# Main.net
KiCad netlist of a schematic drawn in Altium Designer
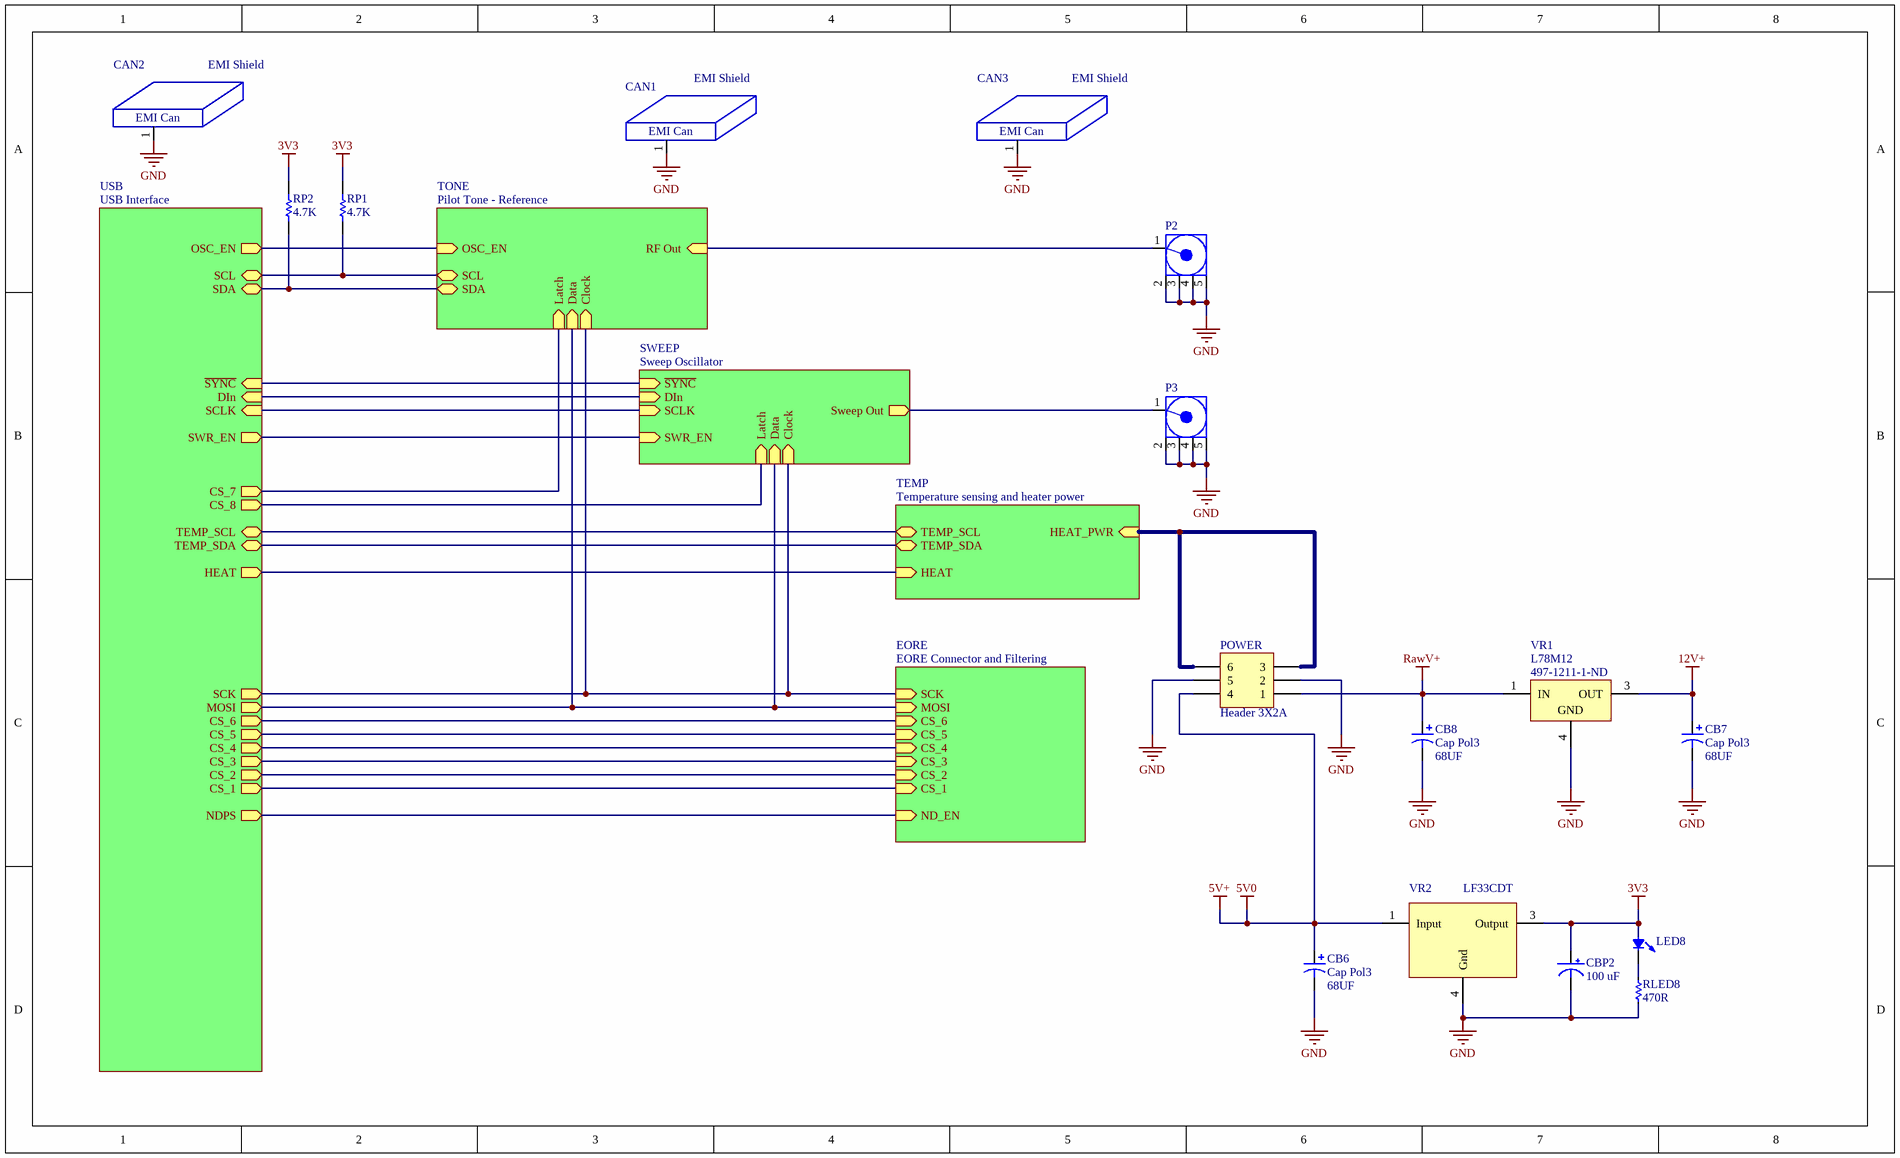
[diagram p0: Main.SchDoc]

(export (version "E")
  (design (tool "Eeschema 10.0.6"))
  (components
    (comp (ref "CAN1")
      (value "EMI Shield")
      (footprint "BMI-S-230-F")
      (description "Laird Technologies 2-part EMI can")
      (libsource (lib "RF Components") (part "BMI-S-205-F RF/EMI Can"))
    )
    (comp (ref "CAN2")
      (value "EMI Shield")
      (footprint "BMI-S-230-F")
      (description "Laird Technologies 2-part EMI can")
      (libsource (lib "RF Components") (part "BMI-S-230-F-R RF/EMI Can"))
    )
    (comp (ref "CAN3")
      (value "EMI Shield")
      (footprint "BMI-S-230-F")
      (description "Laird Technologies 2-part EMI can")
      (libsource (lib "RF Components") (part "BMI-S-230-F-R RF/EMI Can"))
    )
    (comp (ref "CB6")
      (value "Cap Pol3")
      (footprint "V")
      (description "KEMET T520 KO-CAP  Polymer SMT Tantalum")
      (fields (field (name "ALTIUM_VALUE") "68UF") (field (name "VOLTAGE") "10V"))
      (libsource (lib "Miscellaneous Devices") (part "Cap Pol3"))
    )
    (comp (ref "CB7")
      (value "Cap Pol3")
      (footprint "V")
      (description "KEMET T520 KO-CAP  Polymer SMT Tantalum")
      (fields (field (name "ALTIUM_VALUE") "68UF") (field (name "VOLTAGE") "10V"))
      (libsource (lib "Miscellaneous Devices") (part "Cap Pol3"))
    )
    (comp (ref "CB8")
      (value "Cap Pol3")
      (footprint "V")
      (description "KEMET T520 KO-CAP  Polymer SMT Tantalum")
      (fields (field (name "ALTIUM_VALUE") "68UF") (field (name "VOLTAGE") "10V"))
      (libsource (lib "Miscellaneous Devices") (part "Cap Pol3"))
    )
    (comp (ref "CBP2")
      (value "100 uF")
      (footprint "V")
      (libsource (lib "DAQ Sstem") (part "100 uf SMT Panasonic Cap"))
    )
    (comp (ref "LED8")
      (value "LED0")
      (footprint "0603 SMT LED")
      (description "T 1 3/4 LED")
      (fields (field (name "PUBLISHER") "Altium Limited"))
      (libsource (lib "Miscellaneous Devices") (part "LED0"))
    )
    (comp (ref "P2")
      (value "COAX-M")
      (footprint "SMA Jack - PCB Edge - MultiSize")
      (description "RF Coaxial PCB Connector, MMCX; Thru-Hole, Vertical Mount Plug,  50 Ohm Impedance")
      (fields (field (name "PUBLISHER") "Altium Limited"))
      (libsource (lib "Miscellaneous Connectors") (part "COAX-M"))
    )
    (comp (ref "P3")
      (value "COAX-M")
      (footprint "SMA Jack - PCB Edge - MultiSize")
      (description "RF Coaxial PCB Connector, MMCX; Thru-Hole, Vertical Mount Plug,  50 Ohm Impedance")
      (fields (field (name "PUBLISHER") "Altium Limited"))
      (libsource (lib "Miscellaneous Connectors") (part "COAX-M"))
    )
    (comp (ref "POWER")
      (value "Header 3X2A")
      (footprint "Molex Mini-Fit Jr 5569 - 6 Pin, RA")
      (description "Header, 3-Pin, Dual row")
      (fields (field (name "PUBLISHER") "Altium Limited"))
      (libsource (lib "Miscellaneous Connectors") (part "Header 3X2A"))
    )
    (comp (ref "RLED8")
      (value "470R")
      (footprint "0603R")
      (description "Semiconductor Resistor")
      (fields (field (name "Comment") "Res Semi Small") (field (name "PUBLISHER") "Altium Limited"))
      (libsource (lib "Miscellaneous Devices") (part "Res Semi Small"))
    )
    (comp (ref "RP1")
      (value "4.7K")
      (footprint "0603R")
      (description "Semiconductor Resistor")
      (fields (field (name "Comment") "Res Semi") (field (name "PUBLISHER") "Altium Limited"))
      (libsource (lib "Miscellaneous Devices") (part "Res Semi"))
    )
    (comp (ref "RP2")
      (value "4.7K")
      (footprint "0603R")
      (description "Semiconductor Resistor")
      (fields (field (name "Comment") "Res Semi") (field (name "PUBLISHER") "Altium Limited"))
      (libsource (lib "Miscellaneous Devices") (part "Res Semi"))
    )
    (comp (ref "VR1")
      (value "L78M12")
      (footprint "TO228P1000-3_4N")
      (description "Three-Terminal Medium Current Positive Voltage Regulator")
      (fields (field (name "DKPN") "497-1211-1-ND") (field (name "PUBLISHER") "Altium Limited"))
      (libsource (lib "ICs") (part "MC78M05ACDT"))
    )
    (comp (ref "VR2")
      (value "LF33CDT")
      (footprint "TO228P1000-3_4N")
      (description "Very low drop 500 ma voltage regulators")
      (libsource (lib "DAQ System") (part "LF33CDT"))
    )
  )
  (nets
    (net (code "11") (name "/HEAT_PWR") (class "Default")
      (node (ref "POWER") (pin "3") (pinfunction "3_3") (pintype "passive"))
      (node (ref "POWER") (pin "6") (pinfunction "6_6") (pintype "passive"))
    )
    (net (code "15") (name "/RF Out") (class "Default")
      (node (ref "P2") (pin "1") (pinfunction "Signal_1") (pintype "passive"))
    )
    (net (code "17") (name "/SCL") (class "Default")
      (node (ref "RP1") (pin "1") (pinfunction "1_1") (pintype "passive"))
    )
    (net (code "19") (name "/SDA") (class "Default")
      (node (ref "RP2") (pin "1") (pinfunction "1_1") (pintype "passive"))
    )
    (net (code "22") (name "/Sweep Out") (class "Default")
      (node (ref "P3") (pin "1") (pinfunction "Signal_1") (pintype "passive"))
    )
    (net (code "25") (name "3V3") (class "Default")
      (node (ref "CBP2") (pin "1") (pinfunction "1_1") (pintype "passive"))
      (node (ref "LED8") (pin "1") (pinfunction "1_1") (pintype "passive"))
      (node (ref "RP1") (pin "2") (pinfunction "2_2") (pintype "passive"))
      (node (ref "RP2") (pin "2") (pinfunction "2_2") (pintype "passive"))
      (node (ref "VR2") (pin "3") (pinfunction "Output_3") (pintype "power_in"))
    )
    (net (code "26") (name "5V+") (class "Default")
      (node (ref "CB6") (pin "1") (pinfunction "1_1") (pintype "passive"))
      (node (ref "POWER") (pin "4") (pinfunction "4_4") (pintype "passive"))
      (node (ref "VR2") (pin "1") (pinfunction "Input_1") (pintype "power_in"))
    )
    (net (code "27") (name "12V+") (class "Default")
      (node (ref "CB7") (pin "1") (pinfunction "1_1") (pintype "passive"))
      (node (ref "VR1") (pin "3") (pinfunction "OUT_3") (pintype "power_in"))
    )
    (net (code "28") (name "GND") (class "Default")
      (node (ref "CAN1") (pin "1") (pintype "passive"))
      (node (ref "CAN2") (pin "1") (pintype "passive"))
      (node (ref "CAN3") (pin "1") (pintype "passive"))
      (node (ref "CB6") (pin "2") (pinfunction "2_2") (pintype "passive"))
      (node (ref "CB7") (pin "2") (pinfunction "2_2") (pintype "passive"))
      (node (ref "CB8") (pin "2") (pinfunction "2_2") (pintype "passive"))
      (node (ref "CBP2") (pin "2") (pinfunction "2_2") (pintype "passive"))
      (node (ref "P2") (pin "2") (pinfunction "GND_2") (pintype "power_in"))
      (node (ref "P2") (pin "3") (pinfunction "GND_3") (pintype "power_in"))
      (node (ref "P2") (pin "4") (pinfunction "GND_4") (pintype "power_in"))
      (node (ref "P2") (pin "5") (pinfunction "GND_5") (pintype "power_in"))
      (node (ref "P3") (pin "2") (pinfunction "GND_2") (pintype "power_in"))
      (node (ref "P3") (pin "3") (pinfunction "GND_3") (pintype "power_in"))
      (node (ref "P3") (pin "4") (pinfunction "GND_4") (pintype "power_in"))
      (node (ref "P3") (pin "5") (pinfunction "GND_5") (pintype "power_in"))
      (node (ref "POWER") (pin "2") (pinfunction "2_2") (pintype "passive"))
      (node (ref "POWER") (pin "5") (pinfunction "5_5") (pintype "passive"))
      (node (ref "RLED8") (pin "2") (pinfunction "2_2") (pintype "passive"))
      (node (ref "VR1") (pin "4") (pinfunction "GND_4") (pintype "power_in"))
      (node (ref "VR2") (pin "4") (pinfunction "Gnd_4") (pintype "power_in"))
    )
    (net (code "29") (name "Net-(LED8-Pad2)") (class "Default")
      (node (ref "LED8") (pin "2") (pinfunction "2_2") (pintype "passive"))
      (node (ref "RLED8") (pin "1") (pinfunction "1_1") (pintype "passive"))
    )
    (net (code "30") (name "RawV+") (class "Default")
      (node (ref "CB8") (pin "1") (pinfunction "1_1") (pintype "passive"))
      (node (ref "POWER") (pin "1") (pinfunction "1_1") (pintype "passive"))
      (node (ref "VR1") (pin "1") (pinfunction "IN_1") (pintype "power_in"))
    )
  )
)
